# LightBar.net
KiCad netlist of a schematic drawn in EAGLE
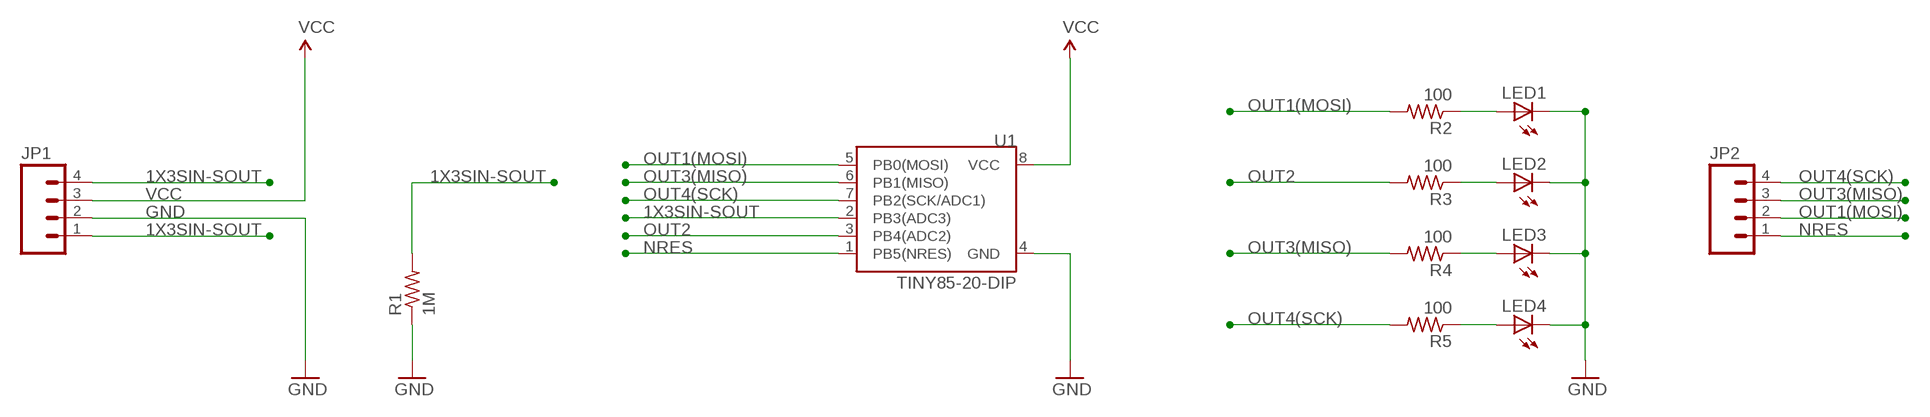
[diagram p0: schematic, sheet 1]

(export (version "E")
  (design (tool "Eeschema 10.0.6"))
  (components
    (comp (ref "JP1")
      (value "M04PTH")
      (footprint "eagle-import:1X04")
      (libsource (lib "eagle-import") (part "M04PTH"))
    )
    (comp (ref "JP2")
      (value "M04PTH")
      (footprint "eagle-import:1X04")
      (libsource (lib "eagle-import") (part "M04PTH"))
    )
    (comp (ref "LED1")
      (value "LEDSQR2X5")
      (footprint "eagle-import:LED2X5")
      (libsource (lib "eagle-import") (part "LEDSQR2X5"))
    )
    (comp (ref "LED2")
      (value "LEDSQR2X5")
      (footprint "eagle-import:LED2X5")
      (libsource (lib "eagle-import") (part "LEDSQR2X5"))
    )
    (comp (ref "LED3")
      (value "LEDSQR2X5")
      (footprint "eagle-import:LED2X5")
      (libsource (lib "eagle-import") (part "LEDSQR2X5"))
    )
    (comp (ref "LED4")
      (value "LEDSQR2X5")
      (footprint "eagle-import:LED2X5")
      (libsource (lib "eagle-import") (part "LEDSQR2X5"))
    )
    (comp (ref "R1")
      (value "1M")
      (footprint "eagle-import:R0603")
      (libsource (lib "eagle-import") (part "R-US_R0603"))
    )
    (comp (ref "R2")
      (value "100")
      (footprint "eagle-import:R0603")
      (libsource (lib "eagle-import") (part "R-US_R0603"))
    )
    (comp (ref "R3")
      (value "100")
      (footprint "eagle-import:R0603")
      (libsource (lib "eagle-import") (part "R-US_R0603"))
    )
    (comp (ref "R4")
      (value "100")
      (footprint "eagle-import:R0603")
      (libsource (lib "eagle-import") (part "R-US_R0603"))
    )
    (comp (ref "R5")
      (value "100")
      (footprint "eagle-import:R0603")
      (libsource (lib "eagle-import") (part "R-US_R0603"))
    )
    (comp (ref "U1")
      (value "TINY85-20-DIP")
      (footprint "eagle-import:DIP08")
      (libsource (lib "eagle-import") (part "ATTINY45TINY85-20-DIP"))
    )
  )
  (nets
    (net (code "1") (name "/1X3SIN-SOUT") (class "Default")
      (node (ref "JP1") (pin "1") (pinfunction "1_1") (pintype "passive"))
      (node (ref "JP1") (pin "4") (pinfunction "4_4") (pintype "passive"))
      (node (ref "R1") (pin "2") (pinfunction "2_2") (pintype "passive"))
      (node (ref "U1") (pin "2") (pinfunction "PB3(ADC3)_2") (pintype "bidirectional"))
    )
    (net (code "2") (name "/NRES") (class "Default")
      (node (ref "JP2") (pin "1") (pinfunction "1_1") (pintype "passive"))
      (node (ref "U1") (pin "1") (pinfunction "PB5(NRES)_1") (pintype "bidirectional"))
    )
    (net (code "3") (name "/OUT1(MOSI)") (class "Default")
      (node (ref "JP2") (pin "2") (pinfunction "2_2") (pintype "passive"))
      (node (ref "R2") (pin "2") (pinfunction "2_2") (pintype "passive"))
      (node (ref "U1") (pin "5") (pinfunction "PB0(MOSI)_5") (pintype "bidirectional"))
    )
    (net (code "4") (name "/OUT2") (class "Default")
      (node (ref "R3") (pin "2") (pinfunction "2_2") (pintype "passive"))
      (node (ref "U1") (pin "3") (pinfunction "PB4(ADC2)_3") (pintype "bidirectional"))
    )
    (net (code "5") (name "/OUT3(MISO)") (class "Default")
      (node (ref "JP2") (pin "3") (pinfunction "3_3") (pintype "passive"))
      (node (ref "R4") (pin "2") (pinfunction "2_2") (pintype "passive"))
      (node (ref "U1") (pin "6") (pinfunction "PB1(MISO)_6") (pintype "bidirectional"))
    )
    (net (code "6") (name "/OUT4(SCK)") (class "Default")
      (node (ref "JP2") (pin "4") (pinfunction "4_4") (pintype "passive"))
      (node (ref "R5") (pin "2") (pinfunction "2_2") (pintype "passive"))
      (node (ref "U1") (pin "7") (pinfunction "PB2(SCK/ADC1)_7") (pintype "bidirectional"))
    )
    (net (code "7") (name "GND") (class "Default")
      (node (ref "JP1") (pin "2") (pinfunction "2_2") (pintype "passive"))
      (node (ref "LED1") (pin "K") (pinfunction "C_K") (pintype "passive"))
      (node (ref "LED2") (pin "K") (pinfunction "C_K") (pintype "passive"))
      (node (ref "LED3") (pin "K") (pinfunction "C_K") (pintype "passive"))
      (node (ref "LED4") (pin "K") (pinfunction "C_K") (pintype "passive"))
      (node (ref "R1") (pin "1") (pinfunction "1_1") (pintype "passive"))
      (node (ref "U1") (pin "4") (pinfunction "GND_4") (pintype "bidirectional"))
    )
    (net (code "8") (name "Net-(LED1-PadA)") (class "Default")
      (node (ref "LED1") (pin "A") (pinfunction "A_A") (pintype "passive"))
      (node (ref "R2") (pin "1") (pinfunction "1_1") (pintype "passive"))
    )
    (net (code "9") (name "Net-(LED2-PadA)") (class "Default")
      (node (ref "LED2") (pin "A") (pinfunction "A_A") (pintype "passive"))
      (node (ref "R3") (pin "1") (pinfunction "1_1") (pintype "passive"))
    )
    (net (code "10") (name "Net-(LED3-PadA)") (class "Default")
      (node (ref "LED3") (pin "A") (pinfunction "A_A") (pintype "passive"))
      (node (ref "R4") (pin "1") (pinfunction "1_1") (pintype "passive"))
    )
    (net (code "11") (name "Net-(LED4-PadA)") (class "Default")
      (node (ref "LED4") (pin "A") (pinfunction "A_A") (pintype "passive"))
      (node (ref "R5") (pin "1") (pinfunction "1_1") (pintype "passive"))
    )
    (net (code "12") (name "VCC") (class "Default")
      (node (ref "JP1") (pin "3") (pinfunction "3_3") (pintype "passive"))
      (node (ref "U1") (pin "8") (pinfunction "VCC_8") (pintype "bidirectional"))
    )
  )
)
